# DM1095_Power_Supply.net
KiCad netlist of a schematic drawn in Altium Designer
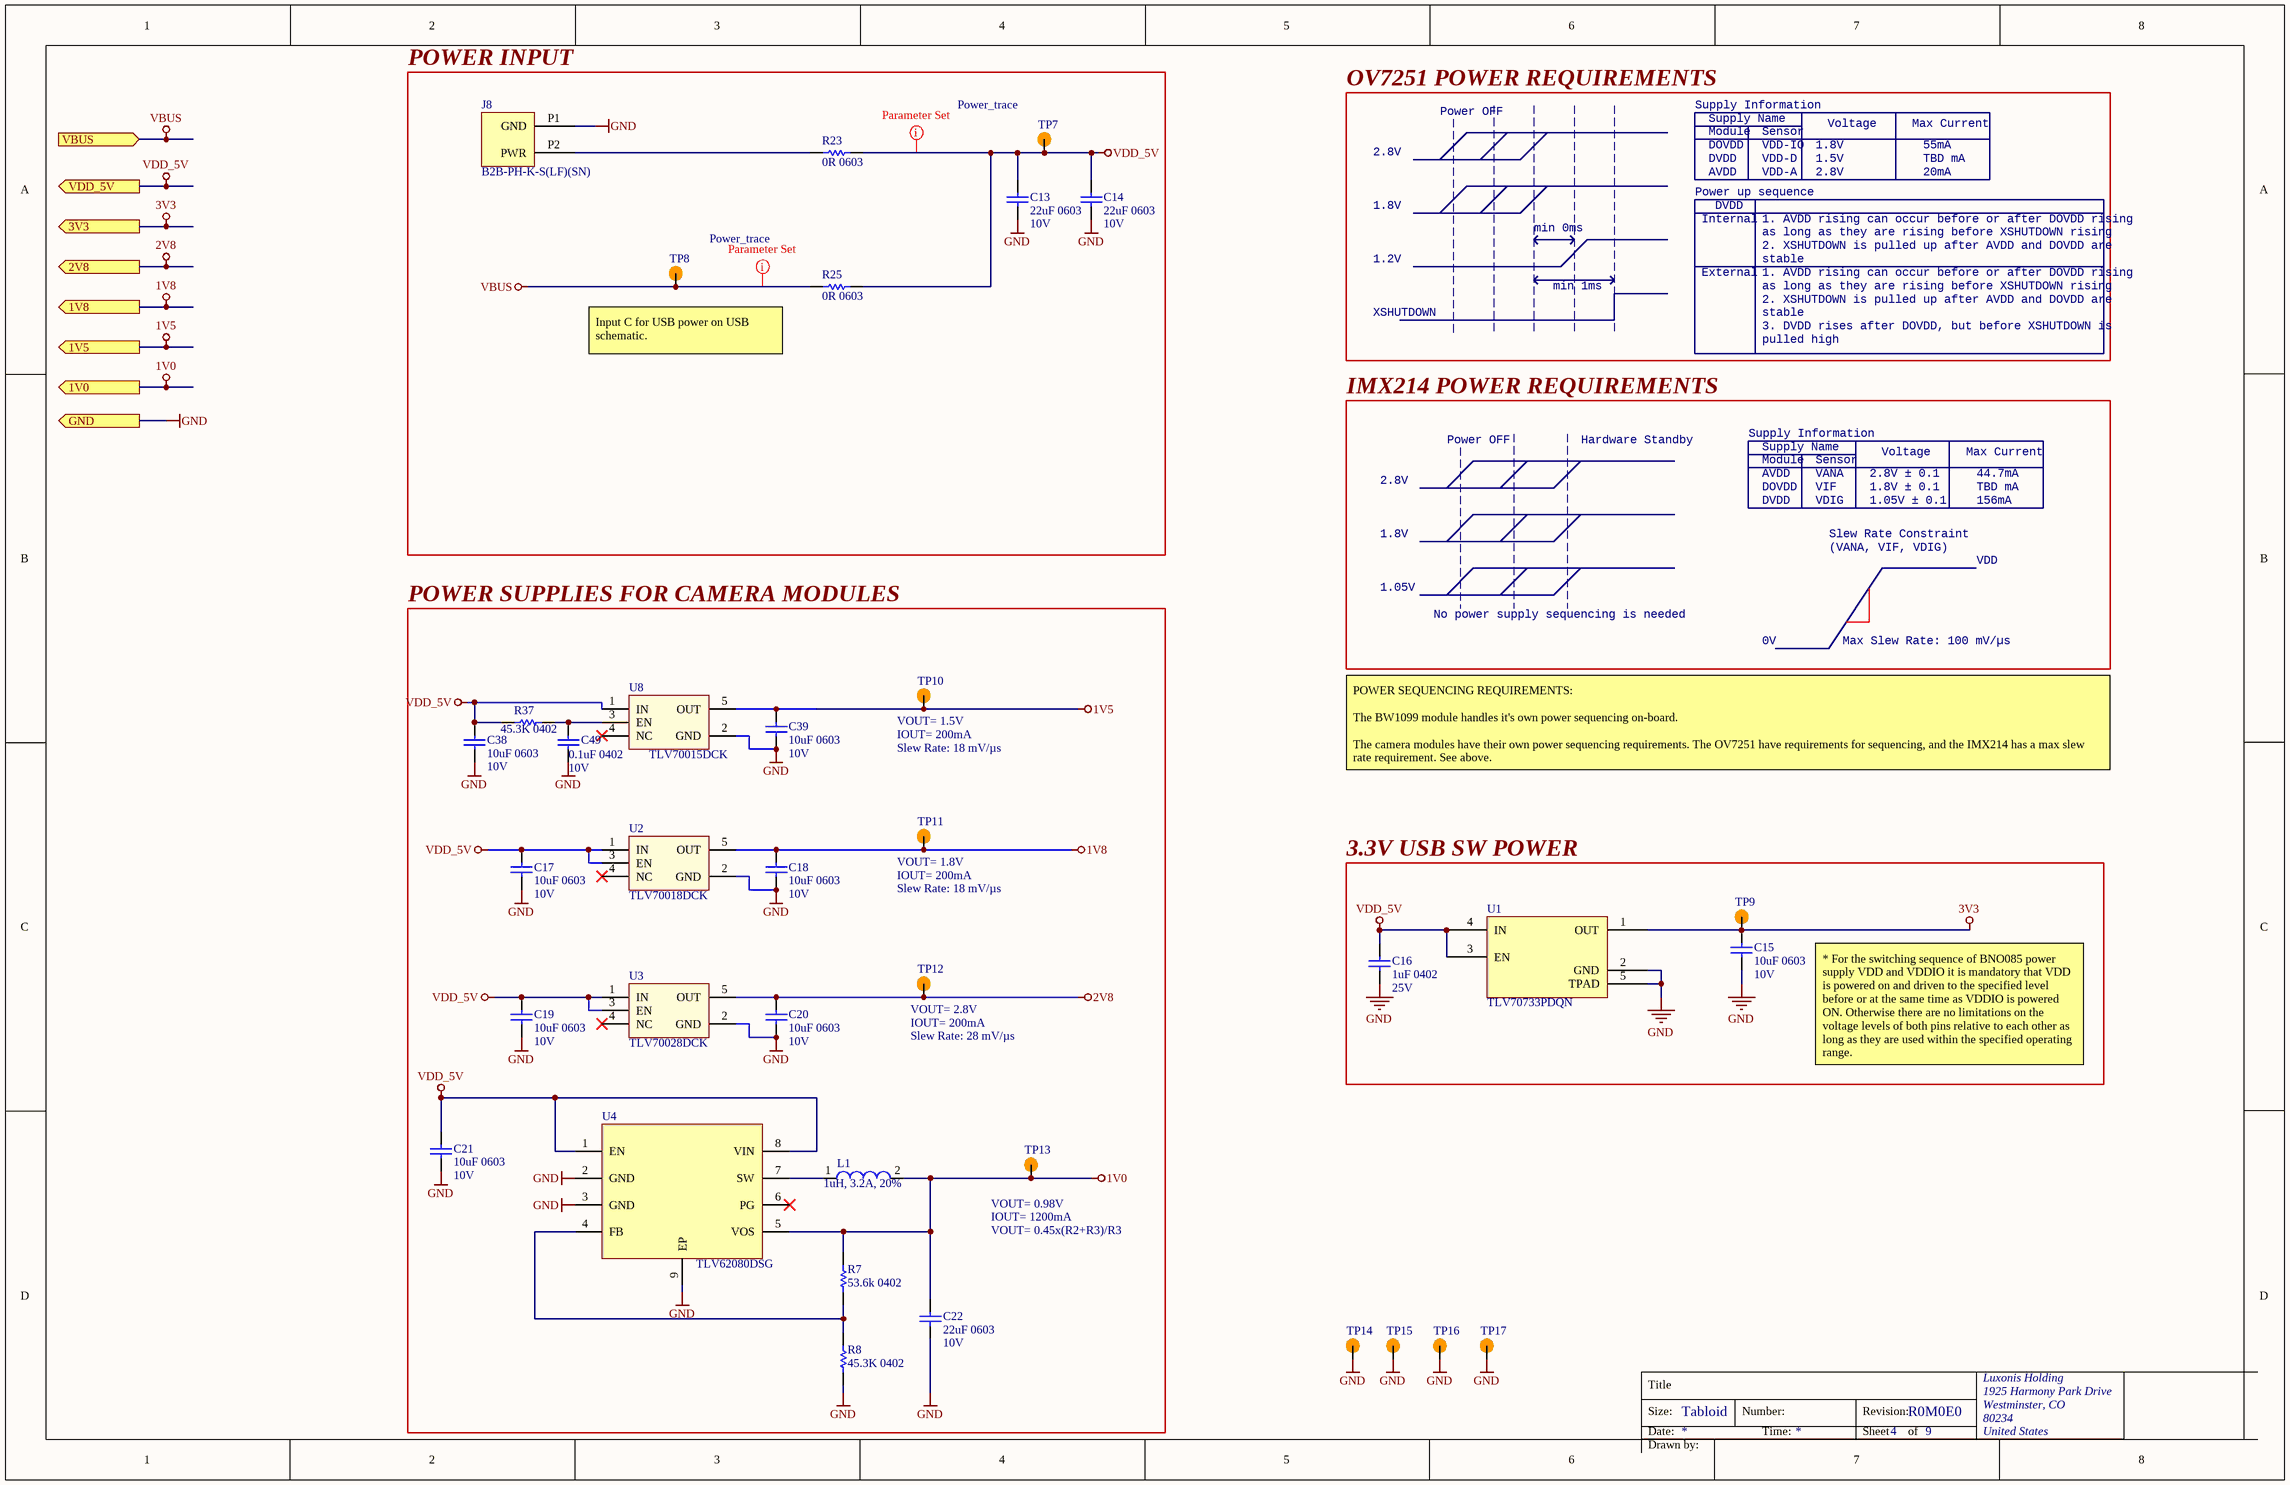
[diagram p0: DM1095_Power_Supply.SchDoc]

(export (version "E")
  (design (tool "Eeschema 10.0.6"))
  (components
    (comp (ref "C13")
      (value "22uF 0603")
      (footprint "CAP_Altium_Vault_Generic:CAPC0603(1608)100_L")
      (description "CAP CER 22UF 10V X5R 0603 20%")
      (fields (field (name "TOLERANCE") "20%") (field (name "VOLTAGE RATING") "10V"))
      (libsource (lib "LuxonisMaster") (part "GRM188R61A226ME15D"))
    )
    (comp (ref "C14")
      (value "22uF 0603")
      (footprint "CAP_Altium_Vault_Generic:CAPC0603(1608)100_L")
      (description "CAP CER 22UF 10V X5R 0603 20%")
      (fields (field (name "TOLERANCE") "20%") (field (name "VOLTAGE RATING") "10V"))
      (libsource (lib "LuxonisMaster") (part "GRM188R61A226ME15D"))
    )
    (comp (ref "C15")
      (value "10uF 0603")
      (footprint "CAP_Altium_Vault_Generic:CAPC0603(1608)100_L")
      (description "CAP CER 10UF 10V X5R 0603 20%")
      (fields (field (name "TOLERANCE") "20%") (field (name "VOLTAGE RATING") "10V"))
      (libsource (lib "LuxonisMaster") (part "GRM188R61A106ME69D"))
    )
    (comp (ref "C16")
      (value "1uF 0402")
      (footprint "CAP_Altium_Vault_Generic:CAPC0402(1005)70_L")
      (description "CAP CER 1UF 25V X5R 0402 10%")
      (fields
        (field (name "TOLERANCE") "10%")
        (field (name "VOLTAGE") "25V")
        (field (name "VOLTAGE RATING") "25V")
      )
      (libsource (lib "LuxonisMaster") (part "GRM155R61E105KA12D"))
    )
    (comp (ref "C17")
      (value "10uF 0603")
      (footprint "CAP_Altium_Vault_Generic:CAPC0603(1608)100_L")
      (description "CAP CER 10UF 10V X5R 0603 20%")
      (fields (field (name "TOLERANCE") "20%") (field (name "VOLTAGE RATING") "10V"))
      (libsource (lib "LuxonisMaster") (part "GRM188R61A106ME69D"))
    )
    (comp (ref "C18")
      (value "10uF 0603")
      (footprint "CAP_Altium_Vault_Generic:CAPC0603(1608)100_L")
      (description "CAP CER 10UF 10V X5R 0603 20%")
      (fields (field (name "TOLERANCE") "20%") (field (name "VOLTAGE RATING") "10V"))
      (libsource (lib "LuxonisMaster") (part "GRM188R61A106ME69D"))
    )
    (comp (ref "C19")
      (value "10uF 0603")
      (footprint "CAP_Altium_Vault_Generic:CAPC0603(1608)100_L")
      (description "CAP CER 10UF 10V X5R 0603 20%")
      (fields (field (name "TOLERANCE") "20%") (field (name "VOLTAGE RATING") "10V"))
      (libsource (lib "LuxonisMaster") (part "GRM188R61A106ME69D"))
    )
    (comp (ref "C20")
      (value "10uF 0603")
      (footprint "CAP_Altium_Vault_Generic:CAPC0603(1608)100_L")
      (description "CAP CER 10UF 10V X5R 0603 20%")
      (fields (field (name "TOLERANCE") "20%") (field (name "VOLTAGE RATING") "10V"))
      (libsource (lib "LuxonisMaster") (part "GRM188R61A106ME69D"))
    )
    (comp (ref "C21")
      (value "10uF 0603")
      (footprint "CAP_Altium_Vault_Generic:CAPC0603(1608)100_L")
      (description "CAP CER 10UF 10V X5R 0603 20%")
      (fields (field (name "TOLERANCE") "20%") (field (name "VOLTAGE RATING") "10V"))
      (libsource (lib "LuxonisMaster") (part "GRM188R61A106ME69D"))
    )
    (comp (ref "C22")
      (value "22uF 0603")
      (footprint "CAP_Altium_Vault_Generic:CAPC0603(1608)100_L")
      (description "CAP CER 22UF 10V X5R 0603 20%")
      (fields (field (name "TOLERANCE") "20%") (field (name "VOLTAGE RATING") "10V"))
      (libsource (lib "LuxonisMaster") (part "GRM188R61A226ME15D"))
    )
    (comp (ref "C38")
      (value "10uF 0603")
      (footprint "CAP_Altium_Vault_Generic:CAPC0603(1608)100_L")
      (description "CAP CER 10UF 10V X5R 0603 20%")
      (fields (field (name "TOLERANCE") "20%") (field (name "VOLTAGE RATING") "10V"))
      (libsource (lib "LuxonisMaster") (part "GRM188R61A106ME69D"))
    )
    (comp (ref "C39")
      (value "10uF 0603")
      (footprint "CAP_Altium_Vault_Generic:CAPC0603(1608)100_L")
      (description "CAP CER 10UF 10V X5R 0603 20%")
      (fields (field (name "TOLERANCE") "20%") (field (name "VOLTAGE RATING") "10V"))
      (libsource (lib "LuxonisMaster") (part "GRM188R61A106ME69D"))
    )
    (comp (ref "C49")
      (value "0.1uF 0402")
      (footprint "CAP_Altium_Vault_Generic:CAPC0402(1005)70_L")
      (description "CAP CER 0.1UF 10V X7R 0402 5%")
      (fields (field (name "TOLERANCE") "5%") (field (name "VOLTAGE RATING") "10V"))
      (libsource (lib "LuxonisMaster") (part "GRM155R71A104JA01D"))
    )
    (comp (ref "J8")
      (value "B2B-PH-K-S(LF)(SN)")
      (footprint "LuxonisMaster:B2B-PH-K-S(LF)(SN)")
      (description "CONN HEADER VERT 2POS 2MM")
      (libsource (lib "LuxonisMaster") (part "B2B-PH-K-S(LF)(SN)"))
    )
    (comp (ref "L1")
      (value "1uH, 3.2A, 20%")
      (footprint "LuxonisMaster:DFE252012P-1R0M=P2")
      (description "FIXED IND 1UH 3.2A 42 MOHM SMD")
      (fields
        (field (name "MANUFACTURER") "Murata")
        (field (name "MANUFACTURER PART NUMBER") "DFE252012P-1R0M=P2")
      )
      (libsource (lib "LuxonisMaster") (part "DFE252012P-1R0M=P2"))
    )
    (comp (ref "R7")
      (value "53.6k 0402")
      (footprint "RES_Altium_Vault_Generic:RESC0402(1005)_L")
      (description "RES SMD 53.6K OHM 1% 1/16W 0402")
      (fields (field (name "TOLERANCE") "1%"))
      (libsource (lib "LuxonisMaster") (part "CRCW040253K6FKED"))
    )
    (comp (ref "R8")
      (value "45.3K 0402")
      (footprint "RES_Altium_Vault_Generic:RESC0402(1005)_L")
      (description "RES SMD 45.3K OHM 1% 1/16W 0402")
      (fields (field (name "TOLERANCE") "1%"))
      (libsource (lib "LuxonisMaster") (part "RC0402FR-0745K3L"))
    )
    (comp (ref "R23")
      (value "0R 0603")
      (footprint "RES_Altium_Vault_Generic:RESC0603(1608)_N")
      (fields (field (name "TOLERANCE") "5%"))
      (libsource (lib "LuxonisMaster") (part "CRCW06030000Z0EA"))
    )
    (comp (ref "R25")
      (value "0R 0603")
      (footprint "RES_Altium_Vault_Generic:RESC0603(1608)_N")
      (fields (field (name "TOLERANCE") "5%"))
      (libsource (lib "LuxonisMaster") (part "CRCW06030000Z0EA"))
    )
    (comp (ref "R37")
      (value "45.3K 0402")
      (footprint "RES_Altium_Vault_Generic:RESC0402(1005)_L")
      (description "RES SMD 45.3K OHM 1% 1/16W 0402")
      (fields (field (name "TOLERANCE") "1%"))
      (libsource (lib "LuxonisMaster") (part "RC0402FR-0745K3L"))
    )
    (comp (ref "TP7")
      (value "TP100_200_NS")
      (footprint "LuxonisMaster:TP100_200_NS")
      (libsource (lib "LuxonisMaster") (part "TEST_POINT"))
    )
    (comp (ref "TP8")
      (value "TP100_200_NS")
      (footprint "LuxonisMaster:TP100_200_NS")
      (libsource (lib "LuxonisMaster") (part "TEST_POINT"))
    )
    (comp (ref "TP9")
      (value "TP100_200_NS")
      (footprint "LuxonisMaster:TP100_200_NS")
      (libsource (lib "LuxonisMaster") (part "TEST_POINT"))
    )
    (comp (ref "TP10")
      (value "TP100_200_NS")
      (footprint "LuxonisMaster:TP100_200_NS")
      (libsource (lib "LuxonisMaster") (part "TEST_POINT"))
    )
    (comp (ref "TP11")
      (value "TP100_200_NS")
      (footprint "LuxonisMaster:TP100_200_NS")
      (libsource (lib "LuxonisMaster") (part "TEST_POINT"))
    )
    (comp (ref "TP12")
      (value "TP100_200_NS")
      (footprint "LuxonisMaster:TP100_200_NS")
      (libsource (lib "LuxonisMaster") (part "TEST_POINT"))
    )
    (comp (ref "TP13")
      (value "TP100_200_NS")
      (footprint "LuxonisMaster:TP100_200_NS")
      (libsource (lib "LuxonisMaster") (part "TEST_POINT"))
    )
    (comp (ref "TP14")
      (value "TP100_200_NS")
      (footprint "LuxonisMaster:TP100_200_NS")
      (libsource (lib "LuxonisMaster") (part "TEST_POINT"))
    )
    (comp (ref "TP15")
      (value "TP100_200_NS")
      (footprint "LuxonisMaster:TP100_200_NS")
      (libsource (lib "LuxonisMaster") (part "TEST_POINT"))
    )
    (comp (ref "TP16")
      (value "TP100_200_NS")
      (footprint "LuxonisMaster:TP100_200_NS")
      (libsource (lib "LuxonisMaster") (part "TEST_POINT"))
    )
    (comp (ref "TP17")
      (value "TP100_200_NS")
      (footprint "LuxonisMaster:TP100_200_NS")
      (libsource (lib "LuxonisMaster") (part "TEST_POINT"))
    )
    (comp (ref "U1")
      (value "TLV70733PDQN")
      (footprint "LuxonisMaster:TLV70733PDQN")
      (description "IC REG LINEAR 3.3V 200MA 4X2SON Linear Voltage Regulator IC  1 Output  200mA 4-X2SON (1x1)")
      (libsource (lib "LuxonisMaster") (part "TLV70733PDQN"))
    )
    (comp (ref "U2")
      (value "TLV70018DCK")
      (footprint "LuxonisMaster:TLV70018DCK")
      (description "IC REG LINEAR 1.8V 200MA SC70-5 Linear Voltage Regulator IC  1 Output  200mA SC-70-5")
      (libsource (lib "LuxonisMaster") (part "TLV70018DCK"))
    )
    (comp (ref "U3")
      (value "TLV70028DCK")
      (footprint "LuxonisMaster:TLV70028DCK")
      (description "IC REG LINEAR 2.8V 200MA SC70-5 Linear Voltage Regulator IC  1 Output  200mA SC-70-5")
      (libsource (lib "LuxonisMaster") (part "TLV70028DCK"))
    )
    (comp (ref "U4")
      (value "TLV62080DSG")
      (footprint "LuxonisMaster:TLV62080DSG")
      (description "IC REG BUCK ADJ 1.2A SYNC 8WSON")
      (libsource (lib "LuxonisMaster") (part "TLV62080DSG"))
    )
    (comp (ref "U8")
      (value "TLV70015DCK")
      (footprint "LuxonisMaster:TLV70015DCK")
      (description "Fixed Positive LDO Regulator, 1.5V, PMOS, PDSO5")
      (libsource (lib "LuxonisMaster") (part "TLV70015DCK"))
    )
  )
  (nets
    (net (code "1") (name "1V0") (class "Default")
      (node (ref "C22") (pin "2") (pinfunction "2_2") (pintype "passive"))
      (node (ref "L1") (pin "2") (pinfunction "2_2") (pintype "passive"))
      (node (ref "R7") (pin "2") (pinfunction "2_2") (pintype "passive"))
      (node (ref "TP13") (pin "1") (pintype "passive"))
      (node (ref "U4") (pin "5") (pinfunction "VOS_5") (pintype "passive"))
    )
    (net (code "2") (name "1V5") (class "Default")
      (node (ref "C39") (pin "2") (pinfunction "2_2") (pintype "passive"))
      (node (ref "TP10") (pin "1") (pintype "passive"))
      (node (ref "U8") (pin "5") (pinfunction "OUT_5") (pintype "passive"))
    )
    (net (code "3") (name "1V8") (class "Default")
      (node (ref "C18") (pin "2") (pinfunction "2_2") (pintype "passive"))
      (node (ref "TP11") (pin "1") (pintype "passive"))
      (node (ref "U2") (pin "5") (pinfunction "OUT_5") (pintype "passive"))
    )
    (net (code "4") (name "2V8") (class "Default")
      (node (ref "C20") (pin "2") (pinfunction "2_2") (pintype "passive"))
      (node (ref "TP12") (pin "1") (pintype "passive"))
      (node (ref "U3") (pin "5") (pinfunction "OUT_5") (pintype "passive"))
    )
    (net (code "5") (name "3V3") (class "Default")
      (node (ref "C15") (pin "2") (pinfunction "2_2") (pintype "passive"))
      (node (ref "TP9") (pin "1") (pintype "passive"))
      (node (ref "U1") (pin "1") (pinfunction "OUT_1") (pintype "power_in"))
    )
    (net (code "6") (name "GND") (class "Default")
      (node (ref "C13") (pin "1") (pinfunction "1_1") (pintype "passive"))
      (node (ref "C14") (pin "1") (pinfunction "1_1") (pintype "passive"))
      (node (ref "C15") (pin "1") (pinfunction "1_1") (pintype "passive"))
      (node (ref "C16") (pin "1") (pinfunction "1_1") (pintype "passive"))
      (node (ref "C17") (pin "1") (pinfunction "1_1") (pintype "passive"))
      (node (ref "C18") (pin "1") (pinfunction "1_1") (pintype "passive"))
      (node (ref "C19") (pin "1") (pinfunction "1_1") (pintype "passive"))
      (node (ref "C20") (pin "1") (pinfunction "1_1") (pintype "passive"))
      (node (ref "C21") (pin "1") (pinfunction "1_1") (pintype "passive"))
      (node (ref "C22") (pin "1") (pinfunction "1_1") (pintype "passive"))
      (node (ref "C38") (pin "1") (pinfunction "1_1") (pintype "passive"))
      (node (ref "C39") (pin "1") (pinfunction "1_1") (pintype "passive"))
      (node (ref "C49") (pin "1") (pinfunction "1_1") (pintype "passive"))
      (node (ref "J8") (pin "P1") (pinfunction "GND_P1") (pintype "passive"))
      (node (ref "R8") (pin "1") (pinfunction "1_1") (pintype "passive"))
      (node (ref "TP14") (pin "1") (pintype "passive"))
      (node (ref "TP15") (pin "1") (pintype "passive"))
      (node (ref "TP16") (pin "1") (pintype "passive"))
      (node (ref "TP17") (pin "1") (pintype "passive"))
      (node (ref "U1") (pin "2") (pinfunction "GND_2") (pintype "power_in"))
      (node (ref "U1") (pin "5") (pinfunction "TPAD_5") (pintype "passive"))
      (node (ref "U2") (pin "2") (pinfunction "GND_2") (pintype "passive"))
      (node (ref "U3") (pin "2") (pinfunction "GND_2") (pintype "passive"))
      (node (ref "U4") (pin "2") (pinfunction "GND_2") (pintype "passive"))
      (node (ref "U4") (pin "3") (pinfunction "GND_3") (pintype "passive"))
      (node (ref "U4") (pin "9") (pinfunction "EP_9") (pintype "passive"))
      (node (ref "U8") (pin "2") (pinfunction "GND_2") (pintype "passive"))
    )
    (net (code "7") (name "Net-(J8-PWR)") (class "Default")
      (node (ref "J8") (pin "P2") (pinfunction "PWR_P2") (pintype "passive"))
      (node (ref "R23") (pin "1") (pinfunction "1_1") (pintype "passive"))
    )
    (net (code "8") (name "Net-(U4-FB)") (class "Default")
      (node (ref "R7") (pin "1") (pinfunction "1_1") (pintype "passive"))
      (node (ref "R8") (pin "2") (pinfunction "2_2") (pintype "passive"))
      (node (ref "U4") (pin "4") (pinfunction "FB_4") (pintype "passive"))
    )
    (net (code "9") (name "Net-(U4-SW)") (class "Default")
      (node (ref "L1") (pin "1") (pinfunction "1_1") (pintype "passive"))
      (node (ref "U4") (pin "7") (pinfunction "SW_7") (pintype "passive"))
    )
    (net (code "10") (name "Net-(U8-EN)") (class "Default")
      (node (ref "C49") (pin "2") (pinfunction "2_2") (pintype "passive"))
      (node (ref "R37") (pin "1") (pinfunction "1_1") (pintype "passive"))
      (node (ref "U8") (pin "3") (pinfunction "EN_3") (pintype "passive"))
    )
    (net (code "11") (name "VBUS") (class "Default")
      (node (ref "R25") (pin "1") (pinfunction "1_1") (pintype "passive"))
      (node (ref "TP8") (pin "1") (pintype "passive"))
    )
    (net (code "12") (name "VDD_5V") (class "Default")
      (node (ref "C13") (pin "2") (pinfunction "2_2") (pintype "passive"))
      (node (ref "C14") (pin "2") (pinfunction "2_2") (pintype "passive"))
      (node (ref "C16") (pin "2") (pinfunction "2_2") (pintype "passive"))
      (node (ref "C17") (pin "2") (pinfunction "2_2") (pintype "passive"))
      (node (ref "C19") (pin "2") (pinfunction "2_2") (pintype "passive"))
      (node (ref "C21") (pin "2") (pinfunction "2_2") (pintype "passive"))
      (node (ref "C38") (pin "2") (pinfunction "2_2") (pintype "passive"))
      (node (ref "R23") (pin "2") (pinfunction "2_2") (pintype "passive"))
      (node (ref "R25") (pin "2") (pinfunction "2_2") (pintype "passive"))
      (node (ref "R37") (pin "2") (pinfunction "2_2") (pintype "passive"))
      (node (ref "TP7") (pin "1") (pintype "passive"))
      (node (ref "U1") (pin "3") (pinfunction "EN_3") (pintype "power_in"))
      (node (ref "U1") (pin "4") (pinfunction "IN_4") (pintype "power_in"))
      (node (ref "U2") (pin "1") (pinfunction "IN_1") (pintype "passive"))
      (node (ref "U2") (pin "3") (pinfunction "EN_3") (pintype "passive"))
      (node (ref "U3") (pin "1") (pinfunction "IN_1") (pintype "passive"))
      (node (ref "U3") (pin "3") (pinfunction "EN_3") (pintype "passive"))
      (node (ref "U4") (pin "1") (pinfunction "EN_1") (pintype "passive"))
      (node (ref "U4") (pin "8") (pinfunction "VIN_8") (pintype "passive"))
      (node (ref "U8") (pin "1") (pinfunction "IN_1") (pintype "passive"))
    )
    (net (code "13") (name "unconnected-(U2-NC-Pad4)") (class "Default")
      (node (ref "U2") (pin "4") (pinfunction "NC_4") (pintype "passive+no_connect"))
    )
    (net (code "14") (name "unconnected-(U3-NC-Pad4)") (class "Default")
      (node (ref "U3") (pin "4") (pinfunction "NC_4") (pintype "passive+no_connect"))
    )
    (net (code "15") (name "unconnected-(U4-PG-Pad6)") (class "Default")
      (node (ref "U4") (pin "6") (pinfunction "PG_6") (pintype "passive+no_connect"))
    )
    (net (code "16") (name "unconnected-(U8-NC-Pad4)") (class "Default")
      (node (ref "U8") (pin "4") (pinfunction "NC_4") (pintype "passive+no_connect"))
    )
  )
)
